# STM32_Lvl-Shft_HUB75.net
KiCad netlist of a schematic drawn in Altium Designer
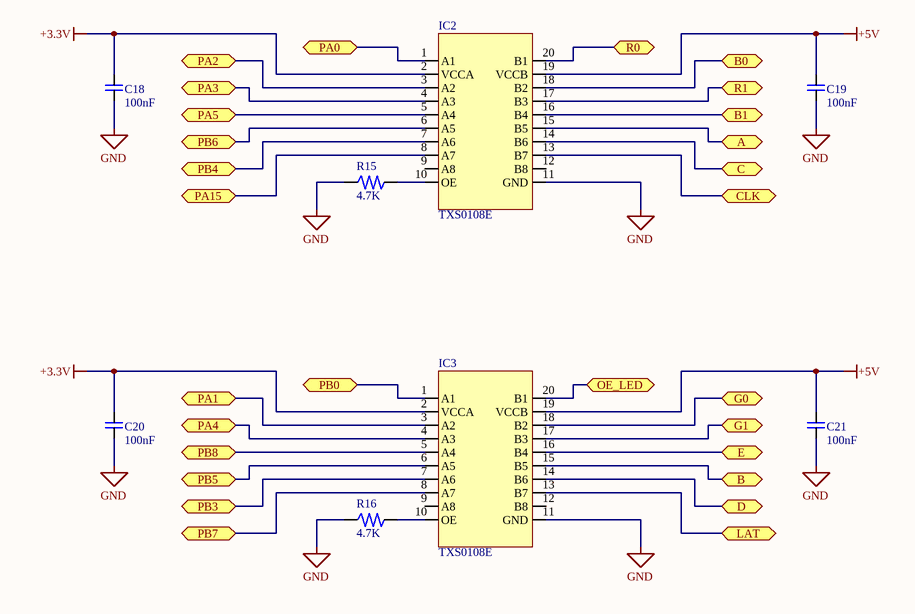
[diagram p0: STM32_Lvl-Shft_HUB75.SchDoc]

(export (version "E")
  (design (tool "Eeschema 10.0.6"))
  (components
    (comp (ref "C18")
      (value "100nF")
      (footprint "SMT_CAP_MODEL_1206(3216)_SAMSUNG")
      (description "SMT Samsung Ceramic Capacitor MODEL *V *nF 1206(3216)  CL31B104KBCNNNC(etc.)")
      (libsource (lib "SMT_CAP_MODEL_1206(3216)_SAMSUNG") (part "SMT_CAP_MODEL_1206(3216)_SAMSUNG"))
    )
    (comp (ref "C19")
      (value "100nF")
      (footprint "SMT_CAP_MODEL_1206(3216)_SAMSUNG")
      (description "SMT Samsung Ceramic Capacitor MODEL *V *nF 1206(3216)  CL31B104KBCNNNC(etc.)")
      (libsource (lib "SMT_CAP_MODEL_1206(3216)_SAMSUNG") (part "SMT_CAP_MODEL_1206(3216)_SAMSUNG"))
    )
    (comp (ref "C20")
      (value "100nF")
      (footprint "SMT_CAP_MODEL_1206(3216)_SAMSUNG")
      (description "SMT Samsung Ceramic Capacitor MODEL *V *nF 1206(3216)  CL31B104KBCNNNC(etc.)")
      (libsource (lib "SMT_CAP_MODEL_1206(3216)_SAMSUNG") (part "SMT_CAP_MODEL_1206(3216)_SAMSUNG"))
    )
    (comp (ref "C21")
      (value "100nF")
      (footprint "SMT_CAP_MODEL_1206(3216)_SAMSUNG")
      (description "SMT Samsung Ceramic Capacitor MODEL *V *nF 1206(3216)  CL31B104KBCNNNC(etc.)")
      (libsource (lib "SMT_CAP_MODEL_1206(3216)_SAMSUNG") (part "SMT_CAP_MODEL_1206(3216)_SAMSUNG"))
    )
    (comp (ref "IC2")
      (value "TXS0108E")
      (footprint "SMT_TXS0108E_IC")
      (description "TXS0108E 8-BIT Bi-Directional Level Shifter 1.2-3.6V(A) 1.65-5.5V(B)")
      (libsource (lib "SMT_TXS0108E_IC") (part "SMT_TXS0108E_IC"))
    )
    (comp (ref "IC3")
      (value "TXS0108E")
      (footprint "SMT_TXS0108E_IC")
      (description "TXS0108E 8-BIT Bi-Directional Level Shifter 1.2-3.6V(A) 1.65-5.5V(B)")
      (libsource (lib "SMT_TXS0108E_IC") (part "SMT_TXS0108E_IC"))
    )
    (comp (ref "R15")
      (value "4.7K")
      (footprint "SMT_RES_MODEL_1206(3216)_ROHM")
      (description "SMT ROHM Resistor MODEL 1206(3216) 1/4W MCR18ERTJ000")
      (libsource (lib "SMT_RES_MODEL_1206(3216)_ROHM") (part "SMT_RES_MODEL_1206(3216)_ROHM"))
    )
    (comp (ref "R16")
      (value "4.7K")
      (footprint "SMT_RES_MODEL_1206(3216)_ROHM")
      (description "SMT ROHM Resistor MODEL 1206(3216) 1/4W MCR18ERTJ000")
      (libsource (lib "SMT_RES_MODEL_1206(3216)_ROHM") (part "SMT_RES_MODEL_1206(3216)_ROHM"))
    )
  )
  (nets
    (net (code "1") (name "+3.3V") (class "Default")
      (node (ref "C18") (pin "1") (pinfunction "1_1") (pintype "passive"))
      (node (ref "C20") (pin "1") (pinfunction "1_1") (pintype "passive"))
      (node (ref "IC2") (pin "2") (pinfunction "VCCA_2") (pintype "passive"))
      (node (ref "IC3") (pin "2") (pinfunction "VCCA_2") (pintype "passive"))
    )
    (net (code "2") (name "+5V") (class "Default")
      (node (ref "C19") (pin "1") (pinfunction "1_1") (pintype "passive"))
      (node (ref "C21") (pin "1") (pinfunction "1_1") (pintype "passive"))
      (node (ref "IC2") (pin "19") (pinfunction "VCCB_19") (pintype "passive"))
      (node (ref "IC3") (pin "19") (pinfunction "VCCB_19") (pintype "passive"))
    )
    (net (code "3") (name "/A") (class "Default")
      (node (ref "IC2") (pin "15") (pinfunction "B5_15") (pintype "passive"))
    )
    (net (code "4") (name "/B") (class "Default")
      (node (ref "IC3") (pin "15") (pinfunction "B5_15") (pintype "passive"))
    )
    (net (code "5") (name "/B0") (class "Default")
      (node (ref "IC2") (pin "18") (pinfunction "B2_18") (pintype "passive"))
    )
    (net (code "6") (name "/B1") (class "Default")
      (node (ref "IC2") (pin "16") (pinfunction "B4_16") (pintype "passive"))
    )
    (net (code "7") (name "/C") (class "Default")
      (node (ref "IC2") (pin "14") (pinfunction "B6_14") (pintype "passive"))
    )
    (net (code "8") (name "/CLK") (class "Default")
      (node (ref "IC2") (pin "13") (pinfunction "B7_13") (pintype "passive"))
    )
    (net (code "9") (name "/D") (class "Default")
      (node (ref "IC3") (pin "14") (pinfunction "B6_14") (pintype "passive"))
    )
    (net (code "10") (name "/E") (class "Default")
      (node (ref "IC3") (pin "16") (pinfunction "B4_16") (pintype "passive"))
    )
    (net (code "11") (name "/G0") (class "Default")
      (node (ref "IC3") (pin "18") (pinfunction "B2_18") (pintype "passive"))
    )
    (net (code "12") (name "/G1") (class "Default")
      (node (ref "IC3") (pin "17") (pinfunction "B3_17") (pintype "passive"))
    )
    (net (code "13") (name "/LAT") (class "Default")
      (node (ref "IC3") (pin "13") (pinfunction "B7_13") (pintype "passive"))
    )
    (net (code "14") (name "/OE_LED") (class "Default")
      (node (ref "IC3") (pin "20") (pinfunction "B1_20") (pintype "passive"))
    )
    (net (code "15") (name "/PA0") (class "Default")
      (node (ref "IC2") (pin "1") (pinfunction "A1_1") (pintype "passive"))
    )
    (net (code "16") (name "/PA1") (class "Default")
      (node (ref "IC3") (pin "3") (pinfunction "A2_3") (pintype "passive"))
    )
    (net (code "17") (name "/PA2") (class "Default")
      (node (ref "IC2") (pin "3") (pinfunction "A2_3") (pintype "passive"))
    )
    (net (code "18") (name "/PA3") (class "Default")
      (node (ref "IC2") (pin "4") (pinfunction "A3_4") (pintype "passive"))
    )
    (net (code "19") (name "/PA4") (class "Default")
      (node (ref "IC3") (pin "4") (pinfunction "A3_4") (pintype "passive"))
    )
    (net (code "20") (name "/PA5") (class "Default")
      (node (ref "IC2") (pin "5") (pinfunction "A4_5") (pintype "passive"))
    )
    (net (code "21") (name "/PA15") (class "Default")
      (node (ref "IC2") (pin "8") (pinfunction "A7_8") (pintype "passive"))
    )
    (net (code "22") (name "/PB0") (class "Default")
      (node (ref "IC3") (pin "1") (pinfunction "A1_1") (pintype "passive"))
    )
    (net (code "23") (name "/PB3") (class "Default")
      (node (ref "IC3") (pin "7") (pinfunction "A6_7") (pintype "passive"))
    )
    (net (code "24") (name "/PB4") (class "Default")
      (node (ref "IC2") (pin "7") (pinfunction "A6_7") (pintype "passive"))
    )
    (net (code "25") (name "/PB5") (class "Default")
      (node (ref "IC3") (pin "6") (pinfunction "A5_6") (pintype "passive"))
    )
    (net (code "26") (name "/PB6") (class "Default")
      (node (ref "IC2") (pin "6") (pinfunction "A5_6") (pintype "passive"))
    )
    (net (code "27") (name "/PB7") (class "Default")
      (node (ref "IC3") (pin "8") (pinfunction "A7_8") (pintype "passive"))
    )
    (net (code "28") (name "/PB8") (class "Default")
      (node (ref "IC3") (pin "5") (pinfunction "A4_5") (pintype "passive"))
    )
    (net (code "29") (name "/R0") (class "Default")
      (node (ref "IC2") (pin "20") (pinfunction "B1_20") (pintype "passive"))
    )
    (net (code "30") (name "/R1") (class "Default")
      (node (ref "IC2") (pin "17") (pinfunction "B3_17") (pintype "passive"))
    )
    (net (code "31") (name "GND") (class "Default")
      (node (ref "C18") (pin "2") (pinfunction "2_2") (pintype "passive"))
      (node (ref "C19") (pin "2") (pinfunction "2_2") (pintype "passive"))
      (node (ref "C20") (pin "2") (pinfunction "2_2") (pintype "passive"))
      (node (ref "C21") (pin "2") (pinfunction "2_2") (pintype "passive"))
      (node (ref "IC2") (pin "11") (pinfunction "GND_11") (pintype "passive"))
      (node (ref "IC3") (pin "11") (pinfunction "GND_11") (pintype "passive"))
      (node (ref "R15") (pin "2") (pinfunction "2_2") (pintype "passive"))
      (node (ref "R16") (pin "2") (pinfunction "2_2") (pintype "passive"))
    )
    (net (code "32") (name "Net-(IC2-OE)") (class "Default")
      (node (ref "IC2") (pin "10") (pinfunction "OE_10") (pintype "passive"))
      (node (ref "R15") (pin "1") (pinfunction "1_1") (pintype "passive"))
    )
    (net (code "33") (name "Net-(IC3-OE)") (class "Default")
      (node (ref "IC3") (pin "10") (pinfunction "OE_10") (pintype "passive"))
      (node (ref "R16") (pin "1") (pinfunction "1_1") (pintype "passive"))
    )
    (net (code "34") (name "unconnected-(IC2-A8-Pad9)") (class "Default")
      (node (ref "IC2") (pin "9") (pinfunction "A8_9") (pintype "passive"))
    )
    (net (code "35") (name "unconnected-(IC2-B8-Pad12)") (class "Default")
      (node (ref "IC2") (pin "12") (pinfunction "B8_12") (pintype "passive"))
    )
    (net (code "36") (name "unconnected-(IC3-A8-Pad9)") (class "Default")
      (node (ref "IC3") (pin "9") (pinfunction "A8_9") (pintype "passive"))
    )
    (net (code "37") (name "unconnected-(IC3-B8-Pad12)") (class "Default")
      (node (ref "IC3") (pin "12") (pinfunction "B8_12") (pintype "passive"))
    )
  )
)
